# CAN.net
KiCad netlist of a schematic drawn in Altium Designer
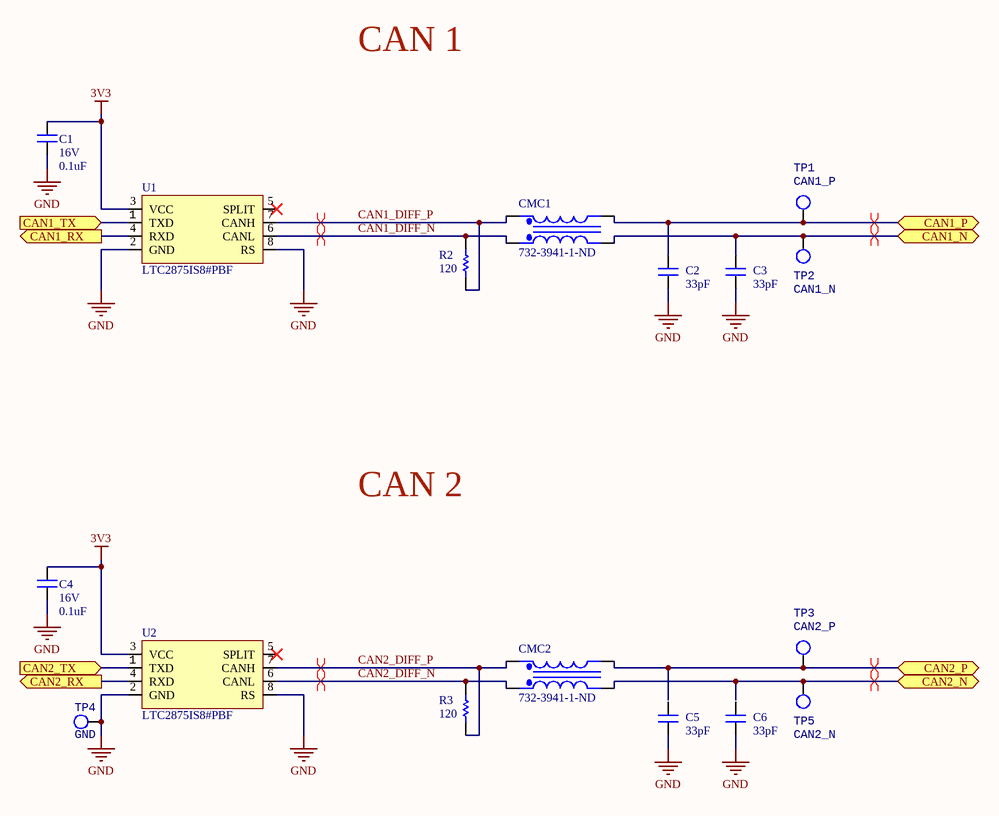
[diagram p0: CAN.SchDoc]

(export (version "E")
  (design (tool "Eeschema 10.0.6"))
  (components
    (comp (ref "C1")
      (value "0.1uF")
      (footprint "CAPC0603(1608)55_N")
      (description "CAP CER 0.1UF 16V X7R 0603")
      (fields (field (name "VOLTAGE RATING") "16V") (field (name "Comment") "CAP_0.1uF_16V_0603"))
      (libsource (lib "UWRT_Schematic_Library_2020") (part "CAP_0.1uF_16V_0603"))
    )
    (comp (ref "C2")
      (value "CAP_33pF_50V_0603")
      (footprint "CAPC0603(1608)55_N")
      (description "CAP CER 33PF 50V C0G/NP0")
      (fields
        (field (name "VOLTAGE") "50V")
        (field (name "TOLERANCE") "5%")
        (field (name "CAPACITANCE") "33pF")
      )
      (libsource (lib "UWRT_Schematic_Library_2020") (part "CAP_33pF_50V_0603"))
    )
    (comp (ref "C3")
      (value "CAP_33pF_50V_0603")
      (footprint "CAPC0603(1608)55_N")
      (description "CAP CER 33PF 50V C0G/NP0")
      (fields
        (field (name "VOLTAGE") "50V")
        (field (name "TOLERANCE") "5%")
        (field (name "CAPACITANCE") "33pF")
      )
      (libsource (lib "UWRT_Schematic_Library_2020") (part "CAP_33pF_50V_0603"))
    )
    (comp (ref "C4")
      (value "0.1uF")
      (footprint "CAPC0603(1608)55_N")
      (description "CAP CER 0.1UF 16V X7R 0603")
      (fields (field (name "VOLTAGE RATING") "16V") (field (name "Comment") "CAP_0.1uF_16V_0603"))
      (libsource (lib "UWRT_Schematic_Library_2020") (part "CAP_0.1uF_16V_0603"))
    )
    (comp (ref "C5")
      (value "CAP_33pF_50V_0603")
      (footprint "CAPC0603(1608)55_N")
      (description "CAP CER 33PF 50V C0G/NP0")
      (fields
        (field (name "VOLTAGE") "50V")
        (field (name "TOLERANCE") "5%")
        (field (name "CAPACITANCE") "33pF")
      )
      (libsource (lib "UWRT_Schematic_Library_2020") (part "CAP_33pF_50V_0603"))
    )
    (comp (ref "C6")
      (value "CAP_33pF_50V_0603")
      (footprint "CAPC0603(1608)55_N")
      (description "CAP CER 33PF 50V C0G/NP0")
      (fields
        (field (name "VOLTAGE") "50V")
        (field (name "TOLERANCE") "5%")
        (field (name "CAPACITANCE") "33pF")
      )
      (libsource (lib "UWRT_Schematic_Library_2020") (part "CAP_33pF_50V_0603"))
    )
    (comp (ref "CMC1")
      (value "CMC_51uH")
      (footprint "744212510")
      (description "CMC 51uH 300MA 2LN SMD")
      (fields (field (name "TOLERANCE") "50%") (field (name "SUPPLIER PART NUMBER 1") "732-3941-1-ND"))
      (libsource (lib "UWRT_Schematic_Library_2020") (part "CMC_51uH"))
    )
    (comp (ref "CMC2")
      (value "CMC_51uH")
      (footprint "744212510")
      (description "CMC 51uH 300MA 2LN SMD")
      (fields (field (name "TOLERANCE") "50%") (field (name "SUPPLIER PART NUMBER 1") "732-3941-1-ND"))
      (libsource (lib "UWRT_Schematic_Library_2020") (part "CMC_51uH"))
    )
    (comp (ref "R2")
      (value "120")
      (footprint "RESC2012X60N")
      (description "RES SMD 120 OHM 1% 1/8W 0805")
      (fields (field (name "RESISTANCE") "120"))
      (libsource (lib "UWRT_Schematic_Library_2020") (part "RES_120R_0805"))
    )
    (comp (ref "R3")
      (value "120")
      (footprint "RESC2012X60N")
      (description "RES SMD 120 OHM 1% 1/8W 0805")
      (fields (field (name "RESISTANCE") "120"))
      (libsource (lib "UWRT_Schematic_Library_2020") (part "RES_120R_0805"))
    )
    (comp (ref "TP1")
      (value "CAN1_P")
      (footprint "TESTPOINT_LOOP")
      (description "Loop testpoint through-hole pad")
      (libsource (lib "UWRT_Schematic_Library_2020") (part "TESTPOINT_LOOP"))
    )
    (comp (ref "TP2")
      (value "CAN1_N")
      (footprint "TESTPOINT_LOOP")
      (description "Loop testpoint through-hole pad")
      (libsource (lib "UWRT_Schematic_Library_2020") (part "TESTPOINT_LOOP"))
    )
    (comp (ref "TP3")
      (value "CAN2_P")
      (footprint "TESTPOINT_LOOP")
      (description "Loop testpoint through-hole pad")
      (libsource (lib "UWRT_Schematic_Library_2020") (part "TESTPOINT_LOOP"))
    )
    (comp (ref "TP4")
      (value "GND")
      (footprint "TESTPOINT_LOOP")
      (description "Loop testpoint through-hole pad")
      (libsource (lib "UWRT_Schematic_Library_2020") (part "TESTPOINT_LOOP"))
    )
    (comp (ref "TP5")
      (value "CAN2_N")
      (footprint "TESTPOINT_LOOP")
      (description "Loop testpoint through-hole pad")
      (libsource (lib "UWRT_Schematic_Library_2020") (part "TESTPOINT_LOOP"))
    )
    (comp (ref "U1")
      (value "IC TXRX CAN")
      (footprint "LT-S8_N")
      (description "IC TXRX CAN 4MBPS 8SO")
      (fields (field (name "MANUFACTURER PART NUMBER 1") "LTC2875IS8#PBF"))
      (libsource (lib "UWRT_Schematic_Library_2020") (part "LTC2875"))
    )
    (comp (ref "U2")
      (value "IC TXRX CAN")
      (footprint "LT-S8_N")
      (description "IC TXRX CAN 4MBPS 8SO")
      (fields (field (name "MANUFACTURER PART NUMBER 1") "LTC2875IS8#PBF"))
      (libsource (lib "UWRT_Schematic_Library_2020") (part "LTC2875"))
    )
  )
  (nets
    (net (code "1") (name "/CAN1_DIFF_N") (class "Default")
      (node (ref "CMC1") (pin "1") (pinfunction "Pri+_1") (pintype "passive"))
      (node (ref "R2") (pin "2") (pinfunction "2_2") (pintype "passive"))
      (node (ref "U1") (pin "6") (pinfunction "CANL_6") (pintype "passive"))
    )
    (net (code "2") (name "/CAN1_DIFF_P") (class "Default")
      (node (ref "CMC1") (pin "3") (pinfunction "Sec+_3") (pintype "passive"))
      (node (ref "R2") (pin "1") (pinfunction "1_1") (pintype "passive"))
      (node (ref "U1") (pin "7") (pinfunction "CANH_7") (pintype "passive"))
    )
    (net (code "3") (name "/CAN1_N") (class "Default")
      (node (ref "C3") (pin "2") (pinfunction "2_2") (pintype "passive"))
      (node (ref "CMC1") (pin "5") (pinfunction "Pri-_5") (pintype "passive"))
      (node (ref "TP2") (pin "1") (pintype "passive"))
    )
    (net (code "4") (name "/CAN1_P") (class "Default")
      (node (ref "C2") (pin "2") (pinfunction "2_2") (pintype "passive"))
      (node (ref "CMC1") (pin "4") (pinfunction "Sec-_4") (pintype "passive"))
      (node (ref "TP1") (pin "1") (pintype "passive"))
    )
    (net (code "5") (name "/CAN1_RX") (class "Default")
      (node (ref "U1") (pin "4") (pinfunction "RXD_4") (pintype "passive"))
    )
    (net (code "6") (name "/CAN1_TX") (class "Default")
      (node (ref "U1") (pin "1") (pinfunction "TXD_1") (pintype "passive"))
    )
    (net (code "7") (name "/CAN2_DIFF_N") (class "Default")
      (node (ref "CMC2") (pin "1") (pinfunction "Pri+_1") (pintype "passive"))
      (node (ref "R3") (pin "2") (pinfunction "2_2") (pintype "passive"))
      (node (ref "U2") (pin "6") (pinfunction "CANL_6") (pintype "passive"))
    )
    (net (code "8") (name "/CAN2_DIFF_P") (class "Default")
      (node (ref "CMC2") (pin "3") (pinfunction "Sec+_3") (pintype "passive"))
      (node (ref "R3") (pin "1") (pinfunction "1_1") (pintype "passive"))
      (node (ref "U2") (pin "7") (pinfunction "CANH_7") (pintype "passive"))
    )
    (net (code "9") (name "/CAN2_N") (class "Default")
      (node (ref "CMC2") (pin "5") (pinfunction "Pri-_5") (pintype "passive"))
      (node (ref "TP5") (pin "1") (pintype "passive"))
    )
    (net (code "10") (name "/CAN2_P") (class "Default")
      (node (ref "CMC2") (pin "4") (pinfunction "Sec-_4") (pintype "passive"))
      (node (ref "TP3") (pin "1") (pintype "passive"))
    )
    (net (code "11") (name "/CAN2_RX") (class "Default")
      (node (ref "U2") (pin "4") (pinfunction "RXD_4") (pintype "passive"))
    )
    (net (code "12") (name "/CAN2_TX") (class "Default")
      (node (ref "U2") (pin "1") (pinfunction "TXD_1") (pintype "passive"))
    )
    (net (code "13") (name "3V3") (class "Default")
      (node (ref "C1") (pin "1") (pinfunction "1_1") (pintype "passive"))
      (node (ref "C4") (pin "1") (pinfunction "1_1") (pintype "passive"))
      (node (ref "U1") (pin "3") (pinfunction "VCC_3") (pintype "passive"))
      (node (ref "U2") (pin "3") (pinfunction "VCC_3") (pintype "passive"))
    )
    (net (code "14") (name "GND") (class "Default")
      (node (ref "C1") (pin "2") (pinfunction "2_2") (pintype "passive"))
      (node (ref "C2") (pin "1") (pinfunction "1_1") (pintype "passive"))
      (node (ref "C3") (pin "1") (pinfunction "1_1") (pintype "passive"))
      (node (ref "C4") (pin "2") (pinfunction "2_2") (pintype "passive"))
      (node (ref "C5") (pin "1") (pinfunction "1_1") (pintype "passive"))
      (node (ref "C6") (pin "1") (pinfunction "1_1") (pintype "passive"))
      (node (ref "TP4") (pin "1") (pintype "passive"))
      (node (ref "U1") (pin "2") (pinfunction "GND_2") (pintype "passive"))
      (node (ref "U1") (pin "8") (pinfunction "RS_8") (pintype "passive"))
      (node (ref "U2") (pin "2") (pinfunction "GND_2") (pintype "passive"))
      (node (ref "U2") (pin "8") (pinfunction "RS_8") (pintype "passive"))
    )
    (net (code "15") (name "unconnected-(C5-Pad2)") (class "Default")
      (node (ref "C5") (pin "2") (pinfunction "2_2") (pintype "passive"))
    )
    (net (code "16") (name "unconnected-(C6-Pad2)") (class "Default")
      (node (ref "C6") (pin "2") (pinfunction "2_2") (pintype "passive"))
    )
    (net (code "17") (name "unconnected-(U1-SPLIT-Pad5)") (class "Default")
      (node (ref "U1") (pin "5") (pinfunction "SPLIT_5") (pintype "passive+no_connect"))
    )
    (net (code "18") (name "unconnected-(U2-SPLIT-Pad5)") (class "Default")
      (node (ref "U2") (pin "5") (pinfunction "SPLIT_5") (pintype "passive+no_connect"))
    )
  )
)
